# Copy_of_CortexM3_dev.net
KiCad netlist of a schematic drawn in Altium Designer
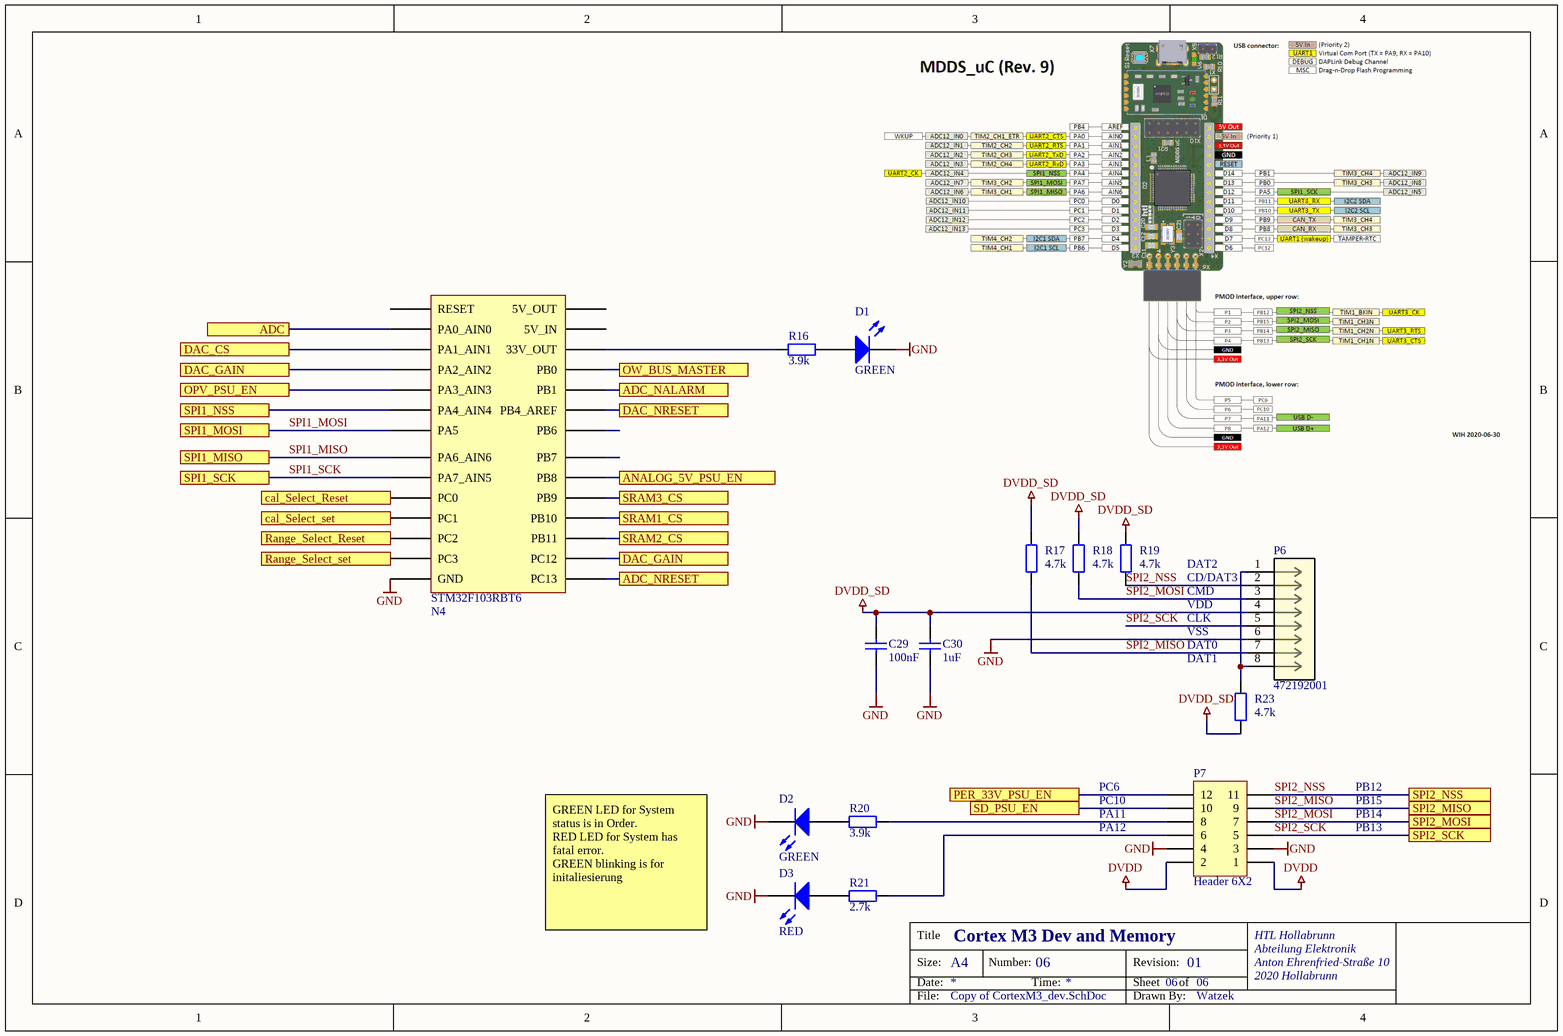
[diagram p0: Copy of CortexM3_dev.SchDoc]

(export (version "E")
  (design (tool "Eeschema 10.0.6"))
  (components
    (comp (ref "C29")
      (value "100nF")
      (footprint "C1206-KUE")
      (description "Capacitor")
      (fields (field (name "MANUFACTURER") "Kemet") (field (name "PUBLISHER") "Altium Limited"))
      (libsource (lib "ExtrapartsKUE_V01") (part "Capacitor"))
    )
    (comp (ref "C30")
      (value "1uF")
      (footprint "C1206-KUE")
      (description "Capacitor")
      (fields (field (name "MANUFACTURER") "Kemet") (field (name "PUBLISHER") "Altium Limited"))
      (libsource (lib "ExtrapartsKUE_V01") (part "Capacitor"))
    )
    (comp (ref "D1")
      (value "GREEN")
      (footprint "6-0805_N-KUE")
      (description "Typical INFRARED GaAs LED")
      (fields (field (name "PUBLISHER") "Altium Limited"))
      (libsource (lib "Miscellaneous Devices") (part "LED0"))
    )
    (comp (ref "D2")
      (value "GREEN")
      (footprint "6-0805_N-KUE")
      (description "Typical INFRARED GaAs LED")
      (fields (field (name "PUBLISHER") "Altium Limited"))
      (libsource (lib "Miscellaneous Devices") (part "LED0"))
    )
    (comp (ref "D3")
      (value "RED")
      (footprint "6-0805_N-KUE")
      (description "Typical INFRARED GaAs LED")
      (fields (field (name "PUBLISHER") "Altium Limited"))
      (libsource (lib "Miscellaneous Devices") (part "LED0"))
    )
    (comp (ref "N4") (value "STM32F103") (footprint "DIP28") (libsource (lib "STM_DEV") (part "STM32F103")))
    (comp (ref "P6")
      (value "472192001")
      (footprint "CONN_47219-2001_MOL")
      (description "1.10mm Pitch microSD Card Connector, Hinge Type, Lead-Free")
      (fields (field (name "COPYRIGHT") "Copyright (C) 2025 Ultra Librarian. All rights reserved."))
      (libsource (lib "472192001") (part "472192001"))
    )
    (comp (ref "P7")
      (value "Header 6X2")
      (footprint "HDR2X6")
      (description "Header, 6-Pin, Dual row")
      (fields (field (name "PUBLISHER") "Altium Limited"))
      (libsource (lib "Miscellaneous Connectors") (part "Header 6X2"))
    )
    (comp (ref "R16")
      (value "3.9k")
      (footprint "C1206-KUE")
      (description "Resistor SMD")
      (fields (field (name "MANUFACTURER") "AVX") (field (name "PUBLISHER") "Altium Limited"))
      (libsource (lib "ExtrapartsKUE_V01") (part "ResistorSMD"))
    )
    (comp (ref "R17")
      (value "4.7k")
      (footprint "C1206-KUE")
      (description "Resistor SMD")
      (fields (field (name "MANUFACTURER") "AVX") (field (name "PUBLISHER") "Altium Limited"))
      (libsource (lib "") (part "ResistorSMD_2"))
    )
    (comp (ref "R18")
      (value "4.7k")
      (footprint "C1206-KUE")
      (description "Resistor SMD")
      (fields (field (name "MANUFACTURER") "AVX") (field (name "PUBLISHER") "Altium Limited"))
      (libsource (lib "") (part "ResistorSMD_2"))
    )
    (comp (ref "R19")
      (value "4.7k")
      (footprint "C1206-KUE")
      (description "Resistor SMD")
      (fields (field (name "MANUFACTURER") "AVX") (field (name "PUBLISHER") "Altium Limited"))
      (libsource (lib "") (part "ResistorSMD_2"))
    )
    (comp (ref "R20")
      (value "3.9k")
      (footprint "C1206-KUE")
      (description "Resistor SMD")
      (fields (field (name "MANUFACTURER") "AVX") (field (name "PUBLISHER") "Altium Limited"))
      (libsource (lib "") (part "ResistorSMD_1"))
    )
    (comp (ref "R21")
      (value "2.7k")
      (footprint "C1206-KUE")
      (description "Resistor SMD")
      (fields (field (name "MANUFACTURER") "AVX") (field (name "PUBLISHER") "Altium Limited"))
      (libsource (lib "") (part "ResistorSMD_1"))
    )
    (comp (ref "R23")
      (value "4.7k")
      (footprint "C1206-KUE")
      (description "Resistor SMD")
      (fields (field (name "MANUFACTURER") "AVX") (field (name "PUBLISHER") "Altium Limited"))
      (libsource (lib "") (part "ResistorSMD_2"))
    )
  )
  (nets
    (net (code "1") (name "/ADC") (class "Default")
      (node (ref "N4") (pin "2") (pinfunction "PA0_AIN0_2") (pintype "passive"))
    )
    (net (code "2") (name "/ADC_NALARM") (class "Default")
      (node (ref "N4") (pin "20") (pinfunction "PB1_20") (pintype "passive"))
    )
    (net (code "3") (name "/ADC_NRESET") (class "Default")
      (node (ref "N4") (pin "27") (pinfunction "PC13_27") (pintype "passive"))
    )
    (net (code "4") (name "/ANALOG_5V_PSU_EN") (class "Default")
      (node (ref "N4") (pin "26") (pinfunction "PB8_26") (pintype "passive"))
    )
    (net (code "5") (name "/DAC_CS") (class "Default")
      (node (ref "N4") (pin "3") (pinfunction "PA1_AIN1_3") (pintype "passive"))
    )
    (net (code "6") (name "/DAC_GAIN") (class "Default")
      (node (ref "N4") (pin "28") (pinfunction "PC12_28") (pintype "passive"))
      (node (ref "N4") (pin "4") (pinfunction "PA2_AIN2_4") (pintype "passive"))
    )
    (net (code "7") (name "/DAC_NRESET") (class "Default")
      (node (ref "N4") (pin "1") (pinfunction "PB4_AREF_1") (pintype "passive"))
    )
    (net (code "8") (name "/OPV_PSU_EN") (class "Default")
      (node (ref "N4") (pin "5") (pinfunction "PA3_AIN3_5") (pintype "passive"))
    )
    (net (code "9") (name "/OW_BUS_MASTER") (class "Default")
      (node (ref "N4") (pin "21") (pinfunction "PB0_21") (pintype "passive"))
    )
    (net (code "10") (name "/PER_33V_PSU_EN") (class "Default")
      (node (ref "P7") (pin "12") (pinfunction "12_12") (pintype "passive"))
    )
    (net (code "11") (name "/Range_Select_Reset") (class "Default")
      (node (ref "N4") (pin "11") (pinfunction "PC2_11") (pintype "passive"))
    )
    (net (code "12") (name "/Range_Select_set") (class "Default")
      (node (ref "N4") (pin "12") (pinfunction "PC3_12") (pintype "passive"))
    )
    (net (code "13") (name "/SD_PSU_EN") (class "Default")
      (node (ref "P7") (pin "10") (pinfunction "10_10") (pintype "passive"))
    )
    (net (code "14") (name "/SPI1_MISO") (class "Default")
      (node (ref "N4") (pin "8") (pinfunction "PA6_AIN6_8") (pintype "passive"))
    )
    (net (code "15") (name "/SPI1_MOSI") (class "Default")
      (node (ref "N4") (pin "22") (pinfunction "PA5_22") (pintype "passive"))
    )
    (net (code "16") (name "/SPI1_NSS") (class "Default")
      (node (ref "N4") (pin "6") (pinfunction "PA4_AIN4_6") (pintype "passive"))
    )
    (net (code "17") (name "/SPI1_SCK") (class "Default")
      (node (ref "N4") (pin "7") (pinfunction "PA7_AIN5_7") (pintype "passive"))
    )
    (net (code "18") (name "/SPI2_MISO") (class "Default")
      (node (ref "P6") (pin "7") (pinfunction "2_7") (pintype "passive"))
      (node (ref "P7") (pin "9") (pinfunction "9_9") (pintype "passive"))
      (node (ref "R17") (pin "2") (pinfunction "2_2") (pintype "passive"))
    )
    (net (code "19") (name "/SPI2_MOSI") (class "Default")
      (node (ref "P6") (pin "3") (pinfunction "6_3") (pintype "passive"))
      (node (ref "P7") (pin "7") (pinfunction "7_7") (pintype "passive"))
      (node (ref "R18") (pin "2") (pinfunction "2_2") (pintype "passive"))
    )
    (net (code "20") (name "/SPI2_NSS") (class "Default")
      (node (ref "P6") (pin "2") (pinfunction "7_2") (pintype "passive"))
      (node (ref "P7") (pin "11") (pinfunction "11_11") (pintype "passive"))
      (node (ref "R19") (pin "2") (pinfunction "2_2") (pintype "passive"))
    )
    (net (code "21") (name "/SPI2_SCK") (class "Default")
      (node (ref "P6") (pin "5") (pinfunction "4_5") (pintype "passive"))
      (node (ref "P7") (pin "5") (pinfunction "5_5") (pintype "passive"))
    )
    (net (code "22") (name "/SRAM1_CS") (class "Default")
      (node (ref "N4") (pin "24") (pinfunction "PB10_24") (pintype "passive"))
    )
    (net (code "23") (name "/SRAM2_CS") (class "Default")
      (node (ref "N4") (pin "23") (pinfunction "PB11_23") (pintype "passive"))
    )
    (net (code "24") (name "/SRAM3_CS") (class "Default")
      (node (ref "N4") (pin "25") (pinfunction "PB9_25") (pintype "passive"))
    )
    (net (code "25") (name "/cal_Select_Reset") (class "Default")
      (node (ref "N4") (pin "9") (pinfunction "PC0_9") (pintype "passive"))
    )
    (net (code "26") (name "/cal_Select_set") (class "Default")
      (node (ref "N4") (pin "10") (pinfunction "PC1_10") (pintype "passive"))
    )
    (net (code "27") (name "DVDD") (class "Default")
      (node (ref "P7") (pin "1") (pinfunction "1_1") (pintype "passive"))
      (node (ref "P7") (pin "2") (pinfunction "2_2") (pintype "passive"))
    )
    (net (code "28") (name "DVDD_SD") (class "Default")
      (node (ref "C29") (pin "2") (pinfunction "2_2") (pintype "passive"))
      (node (ref "C30") (pin "2") (pinfunction "2_2") (pintype "passive"))
      (node (ref "P6") (pin "4") (pinfunction "5_4") (pintype "passive"))
      (node (ref "R17") (pin "1") (pinfunction "1_1") (pintype "passive"))
      (node (ref "R18") (pin "1") (pinfunction "1_1") (pintype "passive"))
      (node (ref "R19") (pin "1") (pinfunction "1_1") (pintype "passive"))
      (node (ref "R23") (pin "2") (pinfunction "2_2") (pintype "passive"))
    )
    (net (code "29") (name "GND") (class "Default")
      (node (ref "C29") (pin "1") (pinfunction "1_1") (pintype "passive"))
      (node (ref "C30") (pin "1") (pinfunction "1_1") (pintype "passive"))
      (node (ref "D1") (pin "2") (pinfunction "K_2") (pintype "passive"))
      (node (ref "D2") (pin "2") (pinfunction "K_2") (pintype "passive"))
      (node (ref "D3") (pin "2") (pinfunction "K_2") (pintype "passive"))
      (node (ref "N4") (pin "18") (pinfunction "GND_18") (pintype "passive"))
      (node (ref "P6") (pin "6") (pinfunction "3_6") (pintype "passive"))
      (node (ref "P7") (pin "3") (pinfunction "3_3") (pintype "passive"))
      (node (ref "P7") (pin "4") (pinfunction "4_4") (pintype "passive"))
    )
    (net (code "30") (name "Net-(D1-A)") (class "Default")
      (node (ref "D1") (pin "1") (pinfunction "A_1") (pintype "passive"))
      (node (ref "R16") (pin "2") (pinfunction "2_2") (pintype "passive"))
    )
    (net (code "31") (name "Net-(D2-A)") (class "Default")
      (node (ref "D2") (pin "1") (pinfunction "A_1") (pintype "passive"))
      (node (ref "R20") (pin "2") (pinfunction "2_2") (pintype "passive"))
    )
    (net (code "32") (name "Net-(D3-A)") (class "Default")
      (node (ref "D3") (pin "1") (pinfunction "A_1") (pintype "passive"))
      (node (ref "R21") (pin "2") (pinfunction "2_2") (pintype "passive"))
    )
    (net (code "33") (name "Net-(N4-33V_OUT)") (class "Default")
      (node (ref "N4") (pin "17") (pinfunction "33V_OUT_17") (pintype "passive"))
      (node (ref "R16") (pin "1") (pinfunction "1_1") (pintype "passive"))
    )
    (net (code "34") (name "Net-(P6-1)") (class "Default")
      (node (ref "P6") (pin "1") (pinfunction "8_1") (pintype "passive"))
      (node (ref "P6") (pin "8") (pinfunction "1_8") (pintype "passive"))
      (node (ref "R23") (pin "1") (pinfunction "1_1") (pintype "passive"))
    )
    (net (code "35") (name "Net-(P7-Pad6)") (class "Default")
      (node (ref "P7") (pin "6") (pinfunction "6_6") (pintype "passive"))
      (node (ref "R21") (pin "1") (pinfunction "1_1") (pintype "passive"))
    )
    (net (code "36") (name "Net-(P7-Pad8)") (class "Default")
      (node (ref "P7") (pin "8") (pinfunction "8_8") (pintype "passive"))
      (node (ref "R20") (pin "1") (pinfunction "1_1") (pintype "passive"))
    )
    (net (code "37") (name "unconnected-(N4-5V_IN-Pad16)") (class "Default")
      (node (ref "N4") (pin "16") (pinfunction "5V_IN_16") (pintype "passive"))
    )
    (net (code "38") (name "unconnected-(N4-5V_OUT-Pad15)") (class "Default")
      (node (ref "N4") (pin "15") (pinfunction "5V_OUT_15") (pintype "passive"))
    )
    (net (code "39") (name "unconnected-(N4-PB6-Pad14)") (class "Default")
      (node (ref "N4") (pin "14") (pinfunction "PB6_14") (pintype "passive"))
    )
    (net (code "40") (name "unconnected-(N4-PB7-Pad13)") (class "Default")
      (node (ref "N4") (pin "13") (pinfunction "PB7_13") (pintype "passive"))
    )
    (net (code "41") (name "unconnected-(N4-RESET-Pad19)") (class "Default")
      (node (ref "N4") (pin "19") (pinfunction "RESET_19") (pintype "passive"))
    )
  )
)
